# esp_0_3.net
KiCad netlist of a schematic drawn in EAGLE
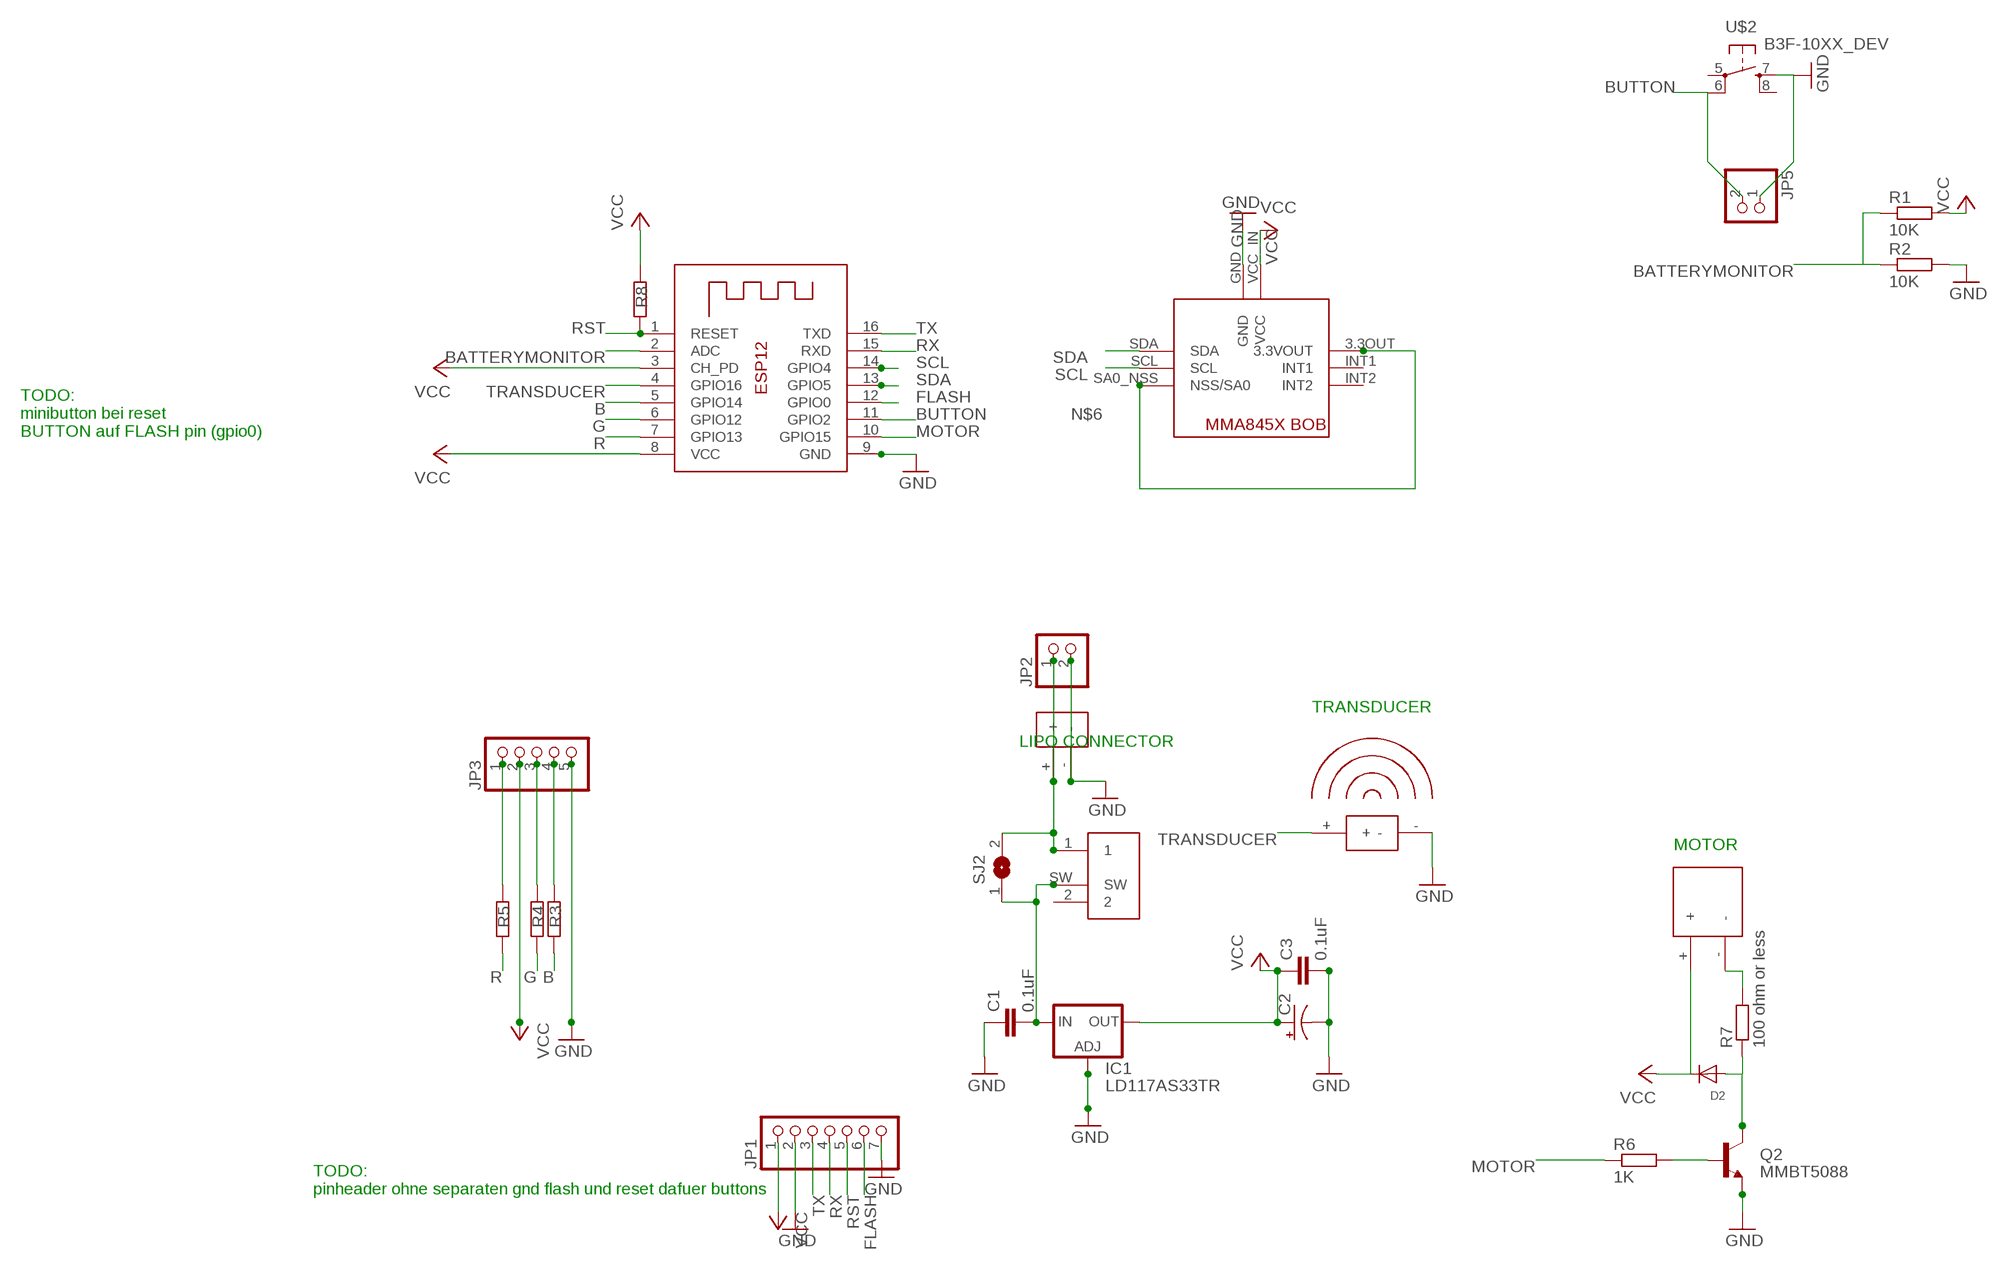
[diagram p0: schematic, sheet 1]

(export (version "E")
  (design (tool "Eeschema 10.0.6"))
  (components
    (comp (ref "C1")
      (value "0.1uF")
      (footprint "eagle-import:0805")
      (libsource (lib "eagle-import") (part "CAP0805"))
    )
    (comp (ref "C2")
      (value "100UF-25V-20%(PTH)")
      (footprint "eagle-import:CPOL-RADIAL-100UF-25V")
      (libsource (lib "eagle-import") (part "100UF-25V-20%(PTH)"))
    )
    (comp (ref "C3")
      (value "0.1uF")
      (footprint "eagle-import:0805")
      (libsource (lib "eagle-import") (part "CAP0805"))
    )
    (comp (ref "D2")
      (value "DIODE_SOD-123FL")
      (footprint "eagle-import:SOD-123FL")
      (libsource (lib "eagle-import") (part "DIODE_SOD-123FL"))
    )
    (comp (ref "IC1")
      (value "LD117AS33TR")
      (footprint "eagle-import:SOT223")
      (libsource (lib "eagle-import") (part "LD117A?S33TR"))
    )
    (comp (ref "JP1")
      (value "PINHD-1X7")
      (footprint "eagle-import:1X07")
      (libsource (lib "eagle-import") (part "PINHD-1X7"))
    )
    (comp (ref "JP2")
      (value "PINHD-1X2")
      (footprint "eagle-import:1X02")
      (libsource (lib "eagle-import") (part "PINHD-1X2"))
    )
    (comp (ref "JP3")
      (value "PINHD-1X5")
      (footprint "eagle-import:1X05")
      (libsource (lib "eagle-import") (part "PINHD-1X5"))
    )
    (comp (ref "JP5")
      (value "PINHD-1X2/90")
      (footprint "eagle-import:1X02_90")
      (libsource (lib "eagle-import") (part "PINHD-1X2/90"))
    )
    (comp (ref "Q2")
      (value "MMBT5088")
      (footprint "eagle-import:SOT23-3")
      (libsource (lib "eagle-import") (part "TRANSISTOR_NPNMMBT5088"))
    )
    (comp (ref "R1")
      (value "10K")
      (footprint "eagle-import:R0805")
      (libsource (lib "eagle-import") (part "R-EU_R0805"))
    )
    (comp (ref "R2")
      (value "10K")
      (footprint "eagle-import:R0805")
      (libsource (lib "eagle-import") (part "R-EU_R0805"))
    )
    (comp (ref "R3")
      (value "1K")
      (footprint "eagle-import:R0805")
      (libsource (lib "eagle-import") (part "R-EU_R0805"))
    )
    (comp (ref "R4")
      (value "1K")
      (footprint "eagle-import:R0805")
      (libsource (lib "eagle-import") (part "R-EU_R0805"))
    )
    (comp (ref "R5")
      (value "1K")
      (footprint "eagle-import:R0805")
      (libsource (lib "eagle-import") (part "R-EU_R0805"))
    )
    (comp (ref "R6")
      (value "1K")
      (footprint "eagle-import:R0805")
      (libsource (lib "eagle-import") (part "R-EU_R0805"))
    )
    (comp (ref "R7")
      (value "100 ohm or less")
      (footprint "eagle-import:R0805")
      (libsource (lib "eagle-import") (part "R-EU_R0805"))
    )
    (comp (ref "R8")
      (value "56K pullup")
      (footprint "eagle-import:R0805")
      (libsource (lib "eagle-import") (part "R-EU_R0805"))
    )
    (comp (ref "SJ2") (value "SJ") (footprint "eagle-import:SJ") (libsource (lib "eagle-import") (part "SJ")))
    (comp (ref "U$1")
      (value "MMA845X_BREAKOUT")
      (footprint "eagle-import:MMA845XBOB")
      (libsource (lib "eagle-import") (part "MMA845X_BREAKOUT"))
    )
    (comp (ref "U$2")
      (value "B3F-10XX_DEV")
      (footprint "eagle-import:B3F-10XX")
      (libsource (lib "eagle-import") (part "B3F-10XX_DEV"))
    )
    (comp (ref "U$8")
      (value "TRANSDUCER")
      (footprint "eagle-import:BMT1205XH7.5")
      (libsource (lib "eagle-import") (part "TRANSDUCER"))
    )
    (comp (ref "U$11")
      (value "MICROSWITCH")
      (footprint "eagle-import:MICR_SCHIEBESCHALTER_CHINA_PAC")
      (libsource (lib "eagle-import") (part "MICROSWITCH"))
    )
    (comp (ref "U$12")
      (value "VIBROMOTOR")
      (footprint "eagle-import:VIBRO")
      (libsource (lib "eagle-import") (part "VIBROMOTOR"))
    )
    (comp (ref "U$13")
      (value "LIPO")
      (footprint "eagle-import:LIPOCON")
      (libsource (lib "eagle-import") (part "LIPO"))
    )
    (comp (ref "X2")
      (value "ESP-12")
      (footprint "eagle-import:ESP-12")
      (libsource (lib "eagle-import") (part "ESP-12"))
    )
  )
  (nets
    (net (code "1") (name "/B") (class "Default")
      (node (ref "R3") (pin "1") (pinfunction "1_1") (pintype "passive"))
      (node (ref "X2") (pin "5") (pinfunction "GPIO14_5") (pintype "bidirectional"))
    )
    (net (code "2") (name "/BATTERYMONITOR") (class "Default")
      (node (ref "R1") (pin "1") (pinfunction "1_1") (pintype "passive"))
      (node (ref "R2") (pin "1") (pinfunction "1_1") (pintype "passive"))
      (node (ref "X2") (pin "2") (pinfunction "ADC_2") (pintype "passive"))
    )
    (net (code "3") (name "/BUTTON") (class "Default")
      (node (ref "JP5") (pin "2") (pinfunction "2_2") (pintype "passive"))
      (node (ref "U$2") (pin "6") (pinfunction "P1_6") (pintype "passive"))
      (node (ref "X2") (pin "11") (pinfunction "GPIO2_11") (pintype "bidirectional"))
    )
    (net (code "4") (name "/FLASH") (class "Default")
      (node (ref "JP1") (pin "6") (pinfunction "6_6") (pintype "passive"))
      (node (ref "X2") (pin "12") (pinfunction "GPIO0_12") (pintype "bidirectional"))
    )
    (net (code "5") (name "/G") (class "Default")
      (node (ref "R4") (pin "1") (pinfunction "1_1") (pintype "passive"))
      (node (ref "X2") (pin "6") (pinfunction "GPIO12_6") (pintype "bidirectional"))
    )
    (net (code "6") (name "/MOTOR") (class "Default")
      (node (ref "R6") (pin "1") (pinfunction "1_1") (pintype "passive"))
      (node (ref "X2") (pin "10") (pinfunction "GPIO15_10") (pintype "bidirectional"))
    )
    (net (code "7") (name "/N$6") (class "Default")
      (node (ref "U$1") (pin "3.3OUT") (pinfunction "3.3VOUT_3.3OUT") (pintype "bidirectional"))
      (node (ref "U$1") (pin "SA0_NSS") (pinfunction "NSS/SA0_SA0_NSS") (pintype "bidirectional"))
    )
    (net (code "8") (name "/R") (class "Default")
      (node (ref "R5") (pin "1") (pinfunction "1_1") (pintype "passive"))
      (node (ref "X2") (pin "7") (pinfunction "GPIO13_7") (pintype "bidirectional"))
    )
    (net (code "9") (name "/RST") (class "Default")
      (node (ref "JP1") (pin "5") (pinfunction "5_5") (pintype "passive"))
      (node (ref "R8") (pin "1") (pinfunction "1_1") (pintype "passive"))
      (node (ref "X2") (pin "1") (pinfunction "RESET_1") (pintype "input"))
    )
    (net (code "10") (name "/RX") (class "Default")
      (node (ref "JP1") (pin "4") (pinfunction "4_4") (pintype "passive"))
      (node (ref "X2") (pin "15") (pinfunction "RXD_15") (pintype "input"))
    )
    (net (code "11") (name "/SCL") (class "Default")
      (node (ref "U$1") (pin "SCL") (pinfunction "SCL_SCL") (pintype "bidirectional"))
      (node (ref "X2") (pin "14") (pinfunction "GPIO4_14") (pintype "bidirectional"))
    )
    (net (code "12") (name "/SDA") (class "Default")
      (node (ref "U$1") (pin "SDA") (pinfunction "SDA_SDA") (pintype "bidirectional"))
      (node (ref "X2") (pin "13") (pinfunction "GPIO5_13") (pintype "bidirectional"))
    )
    (net (code "13") (name "/TRANSDUCER") (class "Default")
      (node (ref "U$8") (pin "+") (pinfunction "+_+") (pintype "bidirectional"))
      (node (ref "X2") (pin "4") (pinfunction "GPIO16_4") (pintype "bidirectional"))
    )
    (net (code "14") (name "/TX") (class "Default")
      (node (ref "JP1") (pin "3") (pinfunction "3_3") (pintype "passive"))
      (node (ref "X2") (pin "16") (pinfunction "TXD_16") (pintype "output"))
    )
    (net (code "15") (name "GND") (class "Default")
      (node (ref "C1") (pin "1") (pinfunction "1_1") (pintype "passive"))
      (node (ref "C2") (pin "2") (pinfunction "-_2") (pintype "passive"))
      (node (ref "C3") (pin "2") (pinfunction "2_2") (pintype "passive"))
      (node (ref "IC1") (pin "1") (pinfunction "ADJ_1") (pintype "input"))
      (node (ref "JP1") (pin "2") (pinfunction "2_2") (pintype "passive"))
      (node (ref "JP1") (pin "7") (pinfunction "7_7") (pintype "passive"))
      (node (ref "JP2") (pin "2") (pinfunction "2_2") (pintype "passive"))
      (node (ref "JP3") (pin "5") (pinfunction "5_5") (pintype "passive"))
      (node (ref "JP5") (pin "1") (pinfunction "1_1") (pintype "passive"))
      (node (ref "Q2") (pin "2") (pinfunction "E_2") (pintype "passive"))
      (node (ref "R2") (pin "2") (pinfunction "2_2") (pintype "passive"))
      (node (ref "U$1") (pin "GND") (pinfunction "GND_GND") (pintype "bidirectional"))
      (node (ref "U$13") (pin "-") (pinfunction "-_-") (pintype "bidirectional"))
      (node (ref "U$2") (pin "7") (pinfunction "S_7") (pintype "passive"))
      (node (ref "U$8") (pin "-") (pinfunction "-_-") (pintype "bidirectional"))
      (node (ref "X2") (pin "9") (pinfunction "GND_9") (pintype "power_in"))
    )
    (net (code "16") (name "Net-(IC1-IN)") (class "Default")
      (node (ref "C1") (pin "2") (pinfunction "2_2") (pintype "passive"))
      (node (ref "IC1") (pin "3") (pinfunction "IN_3") (pintype "input"))
      (node (ref "SJ2") (pin "1") (pinfunction "1_1") (pintype "passive"))
      (node (ref "U$11") (pin "SW") (pinfunction "SW_SW") (pintype "bidirectional"))
    )
    (net (code "17") (name "Net-(JP2-Pad1)") (class "Default")
      (node (ref "JP2") (pin "1") (pinfunction "1_1") (pintype "passive"))
      (node (ref "SJ2") (pin "2") (pinfunction "2_2") (pintype "passive"))
      (node (ref "U$11") (pin "1") (pinfunction "1_1") (pintype "bidirectional"))
      (node (ref "U$13") (pin "+") (pinfunction "+_+") (pintype "bidirectional"))
    )
    (net (code "18") (name "Net-(JP3-Pad1)") (class "Default")
      (node (ref "JP3") (pin "1") (pinfunction "1_1") (pintype "passive"))
      (node (ref "R5") (pin "2") (pinfunction "2_2") (pintype "passive"))
    )
    (net (code "19") (name "Net-(JP3-Pad3)") (class "Default")
      (node (ref "JP3") (pin "3") (pinfunction "3_3") (pintype "passive"))
      (node (ref "R4") (pin "2") (pinfunction "2_2") (pintype "passive"))
    )
    (net (code "20") (name "Net-(JP3-Pad4)") (class "Default")
      (node (ref "JP3") (pin "4") (pinfunction "4_4") (pintype "passive"))
      (node (ref "R3") (pin "2") (pinfunction "2_2") (pintype "passive"))
    )
    (net (code "21") (name "Net-(Q2-B)") (class "Default")
      (node (ref "Q2") (pin "1") (pinfunction "B_1") (pintype "passive"))
      (node (ref "R6") (pin "2") (pinfunction "2_2") (pintype "passive"))
    )
    (net (code "22") (name "Net-(Q2-C)") (class "Default")
      (node (ref "D2") (pin "A") (pinfunction "A_A") (pintype "passive"))
      (node (ref "Q2") (pin "3") (pinfunction "C_3") (pintype "passive"))
      (node (ref "R7") (pin "1") (pinfunction "1_1") (pintype "passive"))
    )
    (net (code "23") (name "Net-(R7-Pad2)") (class "Default")
      (node (ref "R7") (pin "2") (pinfunction "2_2") (pintype "passive"))
      (node (ref "U$12") (pin "-") (pinfunction "-_-") (pintype "bidirectional"))
    )
    (net (code "24") (name "VCC") (class "Default")
      (node (ref "C2") (pin "1") (pinfunction "+_1") (pintype "passive"))
      (node (ref "C3") (pin "1") (pinfunction "1_1") (pintype "passive"))
      (node (ref "D2") (pin "C") (pinfunction "C_C") (pintype "passive"))
      (node (ref "IC1") (pin "4") (pinfunction "OUT_4") (pintype "passive"))
      (node (ref "JP1") (pin "1") (pinfunction "1_1") (pintype "passive"))
      (node (ref "JP3") (pin "2") (pinfunction "2_2") (pintype "passive"))
      (node (ref "R1") (pin "2") (pinfunction "2_2") (pintype "passive"))
      (node (ref "R8") (pin "2") (pinfunction "2_2") (pintype "passive"))
      (node (ref "U$1") (pin "VCC_IN") (pinfunction "VCC_VCC_IN") (pintype "bidirectional"))
      (node (ref "U$12") (pin "+") (pinfunction "+_+") (pintype "bidirectional"))
      (node (ref "X2") (pin "3") (pinfunction "CH_PD_3") (pintype "input"))
      (node (ref "X2") (pin "8") (pinfunction "VCC_8") (pintype "power_in"))
    )
    (net (code "25") (name "unconnected-(U$1-PadINT1)") (class "Default")
      (node (ref "U$1") (pin "INT1") (pinfunction "INT1_INT1") (pintype "bidirectional"))
    )
    (net (code "26") (name "unconnected-(U$1-PadINT2)") (class "Default")
      (node (ref "U$1") (pin "INT2") (pinfunction "INT2_INT2") (pintype "bidirectional"))
    )
    (net (code "27") (name "unconnected-(U$2-P-Pad5)") (class "Default")
      (node (ref "U$2") (pin "5") (pinfunction "P_5") (pintype "passive"))
    )
    (net (code "28") (name "unconnected-(U$2-S1-Pad8)") (class "Default")
      (node (ref "U$2") (pin "8") (pinfunction "S1_8") (pintype "passive"))
    )
    (net (code "29") (name "unconnected-(U$11-Pad2)") (class "Default")
      (node (ref "U$11") (pin "2") (pinfunction "2_2") (pintype "bidirectional"))
    )
  )
)
